# controller_pcb.net
KiCad netlist of a schematic drawn in EAGLE
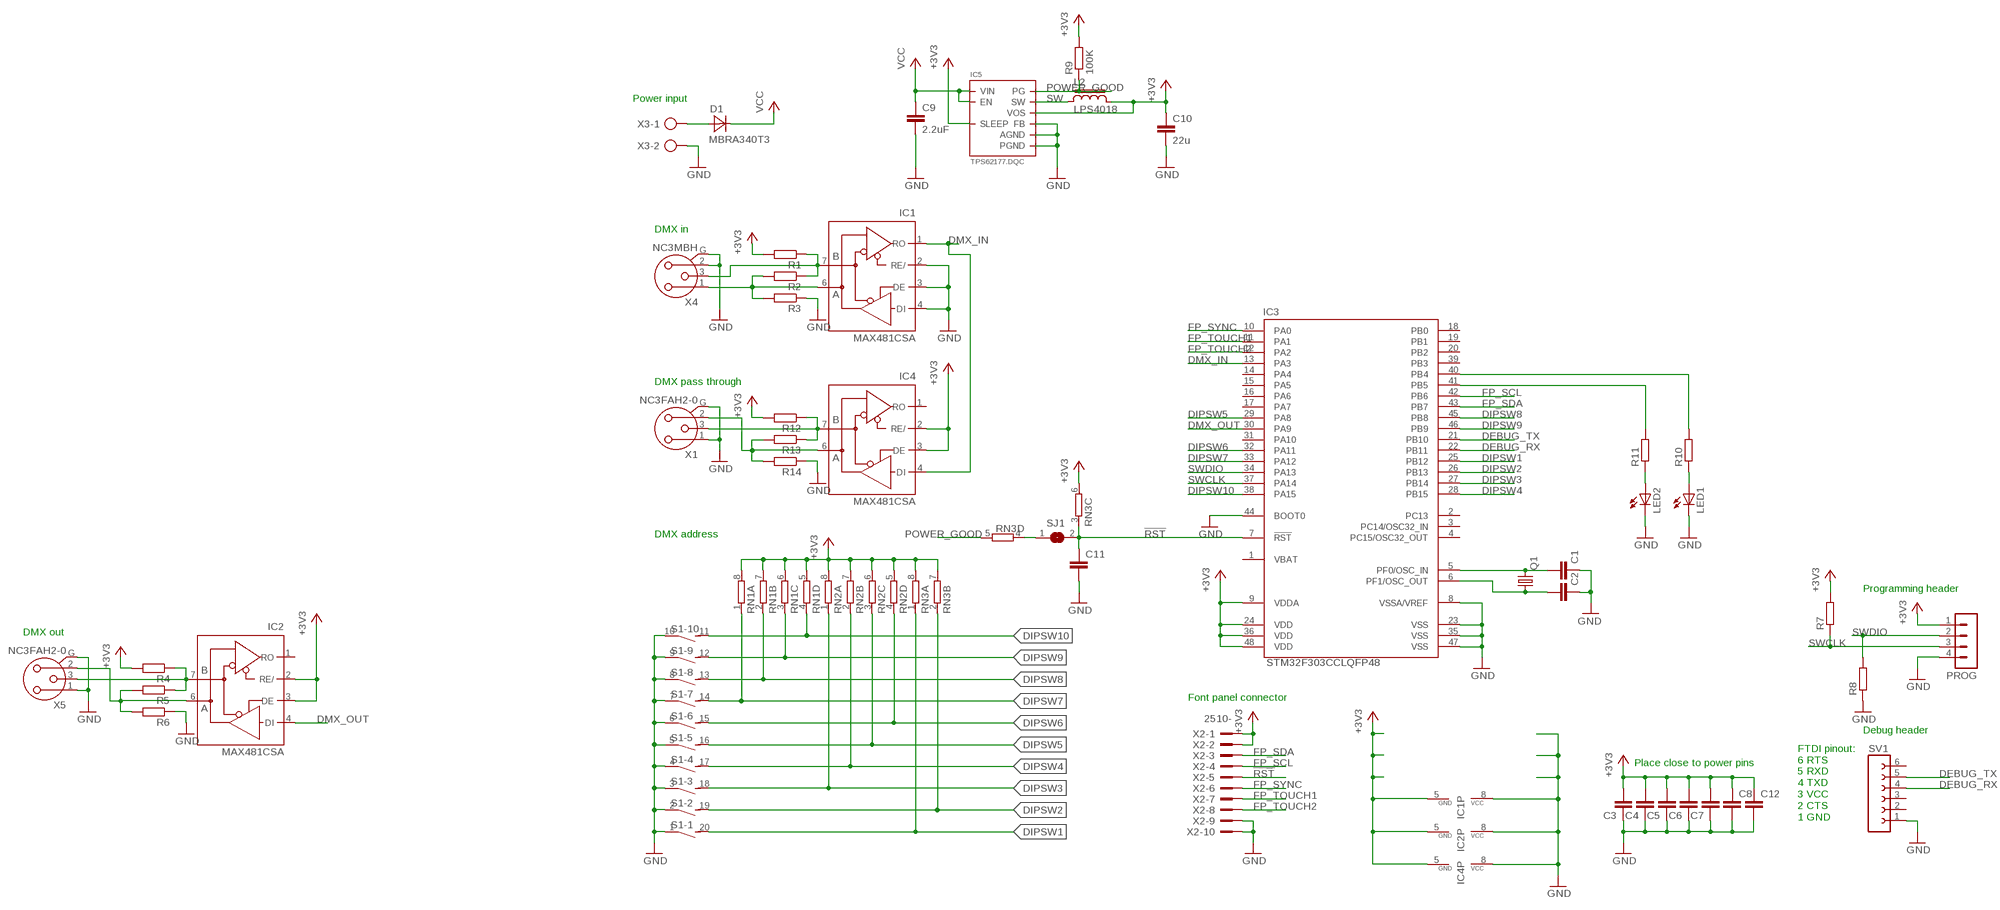
[diagram p0: schematic, sheet 1]

(export (version "E")
  (design (tool "Eeschema 10.0.6"))
  (components
    (comp (ref "C1")
      (value "C-EUC0603K")
      (footprint "eagle-import:C0603K")
      (libsource (lib "eagle-import") (part "C-EUC0603K"))
    )
    (comp (ref "C2")
      (value "C-EUC0603K")
      (footprint "eagle-import:C0603K")
      (libsource (lib "eagle-import") (part "C-EUC0603K"))
    )
    (comp (ref "C3")
      (value "C-EUC0603K")
      (footprint "eagle-import:C0603K")
      (libsource (lib "eagle-import") (part "C-EUC0603K"))
    )
    (comp (ref "C4")
      (value "C-EUC0603K")
      (footprint "eagle-import:C0603K")
      (libsource (lib "eagle-import") (part "C-EUC0603K"))
    )
    (comp (ref "C5")
      (value "C-EUC0603K")
      (footprint "eagle-import:C0603K")
      (libsource (lib "eagle-import") (part "C-EUC0603K"))
    )
    (comp (ref "C6")
      (value "C-EUC0603K")
      (footprint "eagle-import:C0603K")
      (libsource (lib "eagle-import") (part "C-EUC0603K"))
    )
    (comp (ref "C7")
      (value "C-EUC0603K")
      (footprint "eagle-import:C0603K")
      (libsource (lib "eagle-import") (part "C-EUC0603K"))
    )
    (comp (ref "C8")
      (value "C-EUC0603K")
      (footprint "eagle-import:C0603K")
      (libsource (lib "eagle-import") (part "C-EUC0603K"))
    )
    (comp (ref "C9")
      (value "2.2uF")
      (footprint "eagle-import:C1206")
      (libsource (lib "eagle-import") (part "C-EUC1206"))
    )
    (comp (ref "C10")
      (value "22u")
      (footprint "eagle-import:C1206")
      (libsource (lib "eagle-import") (part "C-EUC1206"))
    )
    (comp (ref "C11")
      (value "C-EUC0603K")
      (footprint "eagle-import:C0603K")
      (libsource (lib "eagle-import") (part "C-EUC0603K"))
    )
    (comp (ref "C12")
      (value "C-EUC0603K")
      (footprint "eagle-import:C0603K")
      (libsource (lib "eagle-import") (part "C-EUC0603K"))
    )
    (comp (ref "D1")
      (value "MBRA340T3")
      (footprint "eagle-import:SMA")
      (libsource (lib "eagle-import") (part "MBRA340T3"))
    )
    (comp (ref "IC1")
      (value "MAX481CSA")
      (footprint "eagle-import:SO08")
      (fields (field (name "MF") "MAXIM"))
      (libsource (lib "eagle-import") (part "MAX481CSA"))
    )
    (comp (ref "IC2")
      (value "MAX481CSA")
      (footprint "eagle-import:SO08")
      (fields (field (name "MF") "MAXIM"))
      (libsource (lib "eagle-import") (part "MAX481CSA"))
    )
    (comp (ref "IC3")
      (value "STM32F303CCLQFP48")
      (footprint "eagle-import:LQFP48")
      (libsource (lib "eagle-import") (part "STM32F303CCLQFP48"))
    )
    (comp (ref "IC4")
      (value "MAX481CSA")
      (footprint "eagle-import:SO08")
      (fields (field (name "MF") "MAXIM"))
      (libsource (lib "eagle-import") (part "MAX481CSA"))
    )
    (comp (ref "IC5")
      (value "TPS62177.DQC")
      (footprint "eagle-import:DQC")
      (libsource (lib "eagle-import") (part "TPS62177.DQC"))
    )
    (comp (ref "L2")
      (value "LPS4018")
      (footprint "eagle-import:LPS4018")
      (libsource (lib "eagle-import") (part "LPS4018"))
    )
    (comp (ref "LED1")
      (value "LEDCHIPLED_1206")
      (footprint "eagle-import:CHIPLED_1206")
      (libsource (lib "eagle-import") (part "LEDCHIPLED_1206"))
    )
    (comp (ref "LED2")
      (value "LEDCHIPLED_1206")
      (footprint "eagle-import:CHIPLED_1206")
      (libsource (lib "eagle-import") (part "LEDCHIPLED_1206"))
    )
    (comp (ref "PROG")
      (value "MA04-1")
      (footprint "eagle-import:MA04-1")
      (libsource (lib "eagle-import") (part "MA04-1"))
    )
    (comp (ref "Q1")
      (value "CRYSTALCTS406")
      (footprint "eagle-import:CTS406")
      (libsource (lib "eagle-import") (part "CRYSTALCTS406"))
    )
    (comp (ref "R1")
      (value "R-EU_R0603")
      (footprint "eagle-import:R0603")
      (libsource (lib "eagle-import") (part "R-EU_R0603"))
    )
    (comp (ref "R2")
      (value "R-EU_R0603")
      (footprint "eagle-import:R0603")
      (libsource (lib "eagle-import") (part "R-EU_R0603"))
    )
    (comp (ref "R3")
      (value "R-EU_R0603")
      (footprint "eagle-import:R0603")
      (libsource (lib "eagle-import") (part "R-EU_R0603"))
    )
    (comp (ref "R4")
      (value "R-EU_R0603")
      (footprint "eagle-import:R0603")
      (libsource (lib "eagle-import") (part "R-EU_R0603"))
    )
    (comp (ref "R5")
      (value "R-EU_R0603")
      (footprint "eagle-import:R0603")
      (libsource (lib "eagle-import") (part "R-EU_R0603"))
    )
    (comp (ref "R6")
      (value "R-EU_R0603")
      (footprint "eagle-import:R0603")
      (libsource (lib "eagle-import") (part "R-EU_R0603"))
    )
    (comp (ref "R7")
      (value "R-EU_R0603")
      (footprint "eagle-import:R0603")
      (libsource (lib "eagle-import") (part "R-EU_R0603"))
    )
    (comp (ref "R8")
      (value "R-EU_R0603")
      (footprint "eagle-import:R0603")
      (libsource (lib "eagle-import") (part "R-EU_R0603"))
    )
    (comp (ref "R9")
      (value "100K")
      (footprint "eagle-import:R0603")
      (libsource (lib "eagle-import") (part "R-EU_R0603"))
    )
    (comp (ref "R10")
      (value "R-EU_R0603")
      (footprint "eagle-import:R0603")
      (libsource (lib "eagle-import") (part "R-EU_R0603"))
    )
    (comp (ref "R11")
      (value "R-EU_R0603")
      (footprint "eagle-import:R0603")
      (libsource (lib "eagle-import") (part "R-EU_R0603"))
    )
    (comp (ref "R12")
      (value "R-EU_R0603")
      (footprint "eagle-import:R0603")
      (libsource (lib "eagle-import") (part "R-EU_R0603"))
    )
    (comp (ref "R13")
      (value "R-EU_R0603")
      (footprint "eagle-import:R0603")
      (libsource (lib "eagle-import") (part "R-EU_R0603"))
    )
    (comp (ref "R14")
      (value "R-EU_R0603")
      (footprint "eagle-import:R0603")
      (libsource (lib "eagle-import") (part "R-EU_R0603"))
    )
    (comp (ref "RN1")
      (value "4R-NCAY16")
      (footprint "eagle-import:CAY16")
      (libsource (lib "eagle-import") (part "4R-NCAY16"))
    )
    (comp (ref "RN2")
      (value "4R-NCAY16")
      (footprint "eagle-import:CAY16")
      (libsource (lib "eagle-import") (part "4R-NCAY16"))
    )
    (comp (ref "RN3")
      (value "4R-NCAY16")
      (footprint "eagle-import:CAY16")
      (libsource (lib "eagle-import") (part "4R-NCAY16"))
    )
    (comp (ref "S1")
      (value "DIP10SB")
      (footprint "eagle-import:DIP10SB")
      (libsource (lib "eagle-import") (part "DIP10SB"))
    )
    (comp (ref "SJ1") (value "SJ") (footprint "eagle-import:SJ") (libsource (lib "eagle-import") (part "SJ")))
    (comp (ref "SV1")
      (value "FE06-1")
      (footprint "eagle-import:FE06")
      (libsource (lib "eagle-import") (part "FE06-1"))
    )
    (comp (ref "X1")
      (value "NC3FAH2-0")
      (footprint "eagle-import:NC3FAH2-0")
      (fields (field (name "MPN") "NC3FAH-2-0"))
      (libsource (lib "eagle-import") (part "NC3FAH2-0"))
    )
    (comp (ref "X2")
      (value "2510-")
      (footprint "eagle-import:PAK100_2500-10")
      (fields (field (name "MF") "3M") (field (name "MPN") "2510-6002UB"))
      (libsource (lib "eagle-import") (part "2510-"))
    )
    (comp (ref "X3")
      (value "AK500/2")
      (footprint "eagle-import:AK500_2")
      (libsource (lib "eagle-import") (part "AK500/2"))
    )
    (comp (ref "X4")
      (value "NC3MBH")
      (footprint "eagle-import:NC3MBH")
      (fields (field (name "MF") "NEUTRIK"))
      (libsource (lib "eagle-import") (part "NC3MBH"))
    )
    (comp (ref "X5")
      (value "NC3FAH2-0")
      (footprint "eagle-import:NC3FAH2-0")
      (fields (field (name "MPN") "NC3FAH-2-0"))
      (libsource (lib "eagle-import") (part "NC3FAH2-0"))
    )
  )
  (nets
    (net (code "1") (name "+3V3") (class "Default")
      (node (ref "C10") (pin "1") (pinfunction "1_1") (pintype "passive"))
      (node (ref "C12") (pin "1") (pinfunction "1_1") (pintype "passive"))
      (node (ref "C3") (pin "2") (pinfunction "2_2") (pintype "passive"))
      (node (ref "C4") (pin "2") (pinfunction "2_2") (pintype "passive"))
      (node (ref "C5") (pin "2") (pinfunction "2_2") (pintype "passive"))
      (node (ref "C6") (pin "2") (pinfunction "2_2") (pintype "passive"))
      (node (ref "C7") (pin "2") (pinfunction "2_2") (pintype "passive"))
      (node (ref "C8") (pin "1") (pinfunction "1_1") (pintype "passive"))
      (node (ref "IC1") (pin "5") (pinfunction "GND_5") (pintype "power_in"))
      (node (ref "IC2") (pin "2") (pinfunction "RE/_2") (pintype "input"))
      (node (ref "IC2") (pin "3") (pinfunction "DE_3") (pintype "input"))
      (node (ref "IC2") (pin "5") (pinfunction "GND_5") (pintype "power_in"))
      (node (ref "IC3") (pin "24") (pinfunction "VDD_24") (pintype "power_in"))
      (node (ref "IC3") (pin "36") (pinfunction "VDD_36") (pintype "power_in"))
      (node (ref "IC3") (pin "48") (pinfunction "VDD_48") (pintype "power_in"))
      (node (ref "IC3") (pin "9") (pinfunction "VDDA_9") (pintype "power_in"))
      (node (ref "IC4") (pin "2") (pinfunction "RE/_2") (pintype "input"))
      (node (ref "IC4") (pin "3") (pinfunction "DE_3") (pintype "input"))
      (node (ref "IC4") (pin "5") (pinfunction "GND_5") (pintype "power_in"))
      (node (ref "IC5") (pin "10") (pinfunction "VOS_10") (pintype "bidirectional"))
      (node (ref "IC5") (pin "8") (pinfunction "SLEEP_8") (pintype "bidirectional"))
      (node (ref "L2") (pin "2") (pinfunction "2_2") (pintype "passive"))
      (node (ref "PROG") (pin "1") (pinfunction "1_1") (pintype "passive"))
      (node (ref "R1") (pin "2") (pinfunction "2_2") (pintype "passive"))
      (node (ref "R12") (pin "2") (pinfunction "2_2") (pintype "passive"))
      (node (ref "R4") (pin "2") (pinfunction "2_2") (pintype "passive"))
      (node (ref "R7") (pin "2") (pinfunction "2_2") (pintype "passive"))
      (node (ref "R9") (pin "2") (pinfunction "2_2") (pintype "passive"))
      (node (ref "RN1") (pin "5") (pinfunction "2_5") (pintype "passive"))
      (node (ref "RN1") (pin "6") (pinfunction "2_6") (pintype "passive"))
      (node (ref "RN1") (pin "7") (pinfunction "2_7") (pintype "passive"))
      (node (ref "RN1") (pin "8") (pinfunction "2_8") (pintype "passive"))
      (node (ref "RN2") (pin "5") (pinfunction "2_5") (pintype "passive"))
      (node (ref "RN2") (pin "6") (pinfunction "2_6") (pintype "passive"))
      (node (ref "RN2") (pin "7") (pinfunction "2_7") (pintype "passive"))
      (node (ref "RN2") (pin "8") (pinfunction "2_8") (pintype "passive"))
      (node (ref "RN3") (pin "6") (pinfunction "2_6") (pintype "passive"))
      (node (ref "RN3") (pin "7") (pinfunction "2_7") (pintype "passive"))
      (node (ref "RN3") (pin "8") (pinfunction "2_8") (pintype "passive"))
      (node (ref "X2") (pin "1") (pinfunction "KL_1") (pintype "passive"))
      (node (ref "X2") (pin "2") (pinfunction "KL_2") (pintype "passive"))
    )
    (net (code "2") (name "/DEBUG_RX") (class "Default")
      (node (ref "IC3") (pin "22") (pinfunction "PB11_22") (pintype "bidirectional"))
      (node (ref "SV1") (pin "4") (pinfunction "4_4") (pintype "passive"))
    )
    (net (code "3") (name "/DEBUG_TX") (class "Default")
      (node (ref "IC3") (pin "21") (pinfunction "PB10_21") (pintype "bidirectional"))
      (node (ref "SV1") (pin "5") (pinfunction "5_5") (pintype "passive"))
    )
    (net (code "4") (name "/DMX_IN") (class "Default")
      (node (ref "IC1") (pin "1") (pinfunction "RO_1") (pintype "output"))
      (node (ref "IC3") (pin "13") (pinfunction "PA3_13") (pintype "bidirectional"))
      (node (ref "IC4") (pin "4") (pinfunction "DI_4") (pintype "input"))
    )
    (net (code "5") (name "/DMX_OUT") (class "Default")
      (node (ref "IC2") (pin "4") (pinfunction "DI_4") (pintype "input"))
      (node (ref "IC3") (pin "30") (pinfunction "PA9_30") (pintype "bidirectional"))
    )
    (net (code "6") (name "/FP_SCL") (class "Default")
      (node (ref "IC3") (pin "42") (pinfunction "PB6_42") (pintype "bidirectional"))
      (node (ref "X2") (pin "4") (pinfunction "KL_4") (pintype "passive"))
    )
    (net (code "7") (name "/FP_SDA") (class "Default")
      (node (ref "IC3") (pin "43") (pinfunction "PB7_43") (pintype "bidirectional"))
      (node (ref "X2") (pin "3") (pinfunction "KL_3") (pintype "passive"))
    )
    (net (code "8") (name "/FP_SYNC") (class "Default")
      (node (ref "IC3") (pin "10") (pinfunction "PA0_10") (pintype "bidirectional"))
      (node (ref "X2") (pin "6") (pinfunction "KL_6") (pintype "passive"))
    )
    (net (code "9") (name "/FP_TOUCH1") (class "Default")
      (node (ref "IC3") (pin "11") (pinfunction "PA1_11") (pintype "bidirectional"))
      (node (ref "X2") (pin "7") (pinfunction "KL_7") (pintype "passive"))
    )
    (net (code "10") (name "/FP_TOUCH2") (class "Default")
      (node (ref "IC3") (pin "12") (pinfunction "PA2_12") (pintype "bidirectional"))
      (node (ref "X2") (pin "8") (pinfunction "KL_8") (pintype "passive"))
    )
    (net (code "11") (name "/POWER_GOOD") (class "Default")
      (node (ref "IC5") (pin "7") (pinfunction "PG_7") (pintype "bidirectional"))
      (node (ref "R9") (pin "1") (pinfunction "1_1") (pintype "passive"))
      (node (ref "RN3") (pin "5") (pinfunction "2_5") (pintype "passive"))
    )
    (net (code "12") (name "/SW") (class "Default")
      (node (ref "IC5") (pin "9") (pinfunction "SW_9") (pintype "bidirectional"))
      (node (ref "L2") (pin "1") (pinfunction "1_1") (pintype "passive"))
    )
    (net (code "13") (name "/SWCLK") (class "Default")
      (node (ref "IC3") (pin "37") (pinfunction "PA14_37") (pintype "bidirectional"))
      (node (ref "PROG") (pin "3") (pinfunction "3_3") (pintype "passive"))
      (node (ref "R7") (pin "1") (pinfunction "1_1") (pintype "passive"))
    )
    (net (code "14") (name "/SWDIO") (class "Default")
      (node (ref "IC3") (pin "34") (pinfunction "PA13_34") (pintype "bidirectional"))
      (node (ref "PROG") (pin "2") (pinfunction "2_2") (pintype "passive"))
      (node (ref "R8") (pin "2") (pinfunction "2_2") (pintype "passive"))
    )
    (net (code "15") (name "/~{RST}") (class "Default")
      (node (ref "C11") (pin "1") (pinfunction "1_1") (pintype "passive"))
      (node (ref "IC3") (pin "7") (pinfunction "~{RST}_7") (pintype "bidirectional"))
      (node (ref "RN3") (pin "3") (pinfunction "1_3") (pintype "passive"))
      (node (ref "SJ1") (pin "2") (pinfunction "2_2") (pintype "passive"))
      (node (ref "X2") (pin "5") (pinfunction "KL_5") (pintype "passive"))
    )
    (net (code "16") (name "DIPSW1") (class "Default")
      (node (ref "IC3") (pin "25") (pinfunction "PB12_25") (pintype "bidirectional"))
      (node (ref "RN3") (pin "1") (pinfunction "1_1") (pintype "passive"))
      (node (ref "S1") (pin "20") (pinfunction "2_20") (pintype "passive"))
    )
    (net (code "17") (name "DIPSW2") (class "Default")
      (node (ref "IC3") (pin "26") (pinfunction "PB13_26") (pintype "bidirectional"))
      (node (ref "RN3") (pin "2") (pinfunction "1_2") (pintype "passive"))
      (node (ref "S1") (pin "19") (pinfunction "2_19") (pintype "passive"))
    )
    (net (code "18") (name "DIPSW3") (class "Default")
      (node (ref "IC3") (pin "27") (pinfunction "PB14_27") (pintype "bidirectional"))
      (node (ref "RN2") (pin "1") (pinfunction "1_1") (pintype "passive"))
      (node (ref "S1") (pin "18") (pinfunction "2_18") (pintype "passive"))
    )
    (net (code "19") (name "DIPSW4") (class "Default")
      (node (ref "IC3") (pin "28") (pinfunction "PB15_28") (pintype "bidirectional"))
      (node (ref "RN2") (pin "2") (pinfunction "1_2") (pintype "passive"))
      (node (ref "S1") (pin "17") (pinfunction "2_17") (pintype "passive"))
    )
    (net (code "20") (name "DIPSW5") (class "Default")
      (node (ref "IC3") (pin "29") (pinfunction "PA8_29") (pintype "bidirectional"))
      (node (ref "RN2") (pin "3") (pinfunction "1_3") (pintype "passive"))
      (node (ref "S1") (pin "16") (pinfunction "2_16") (pintype "passive"))
    )
    (net (code "21") (name "DIPSW6") (class "Default")
      (node (ref "IC3") (pin "32") (pinfunction "PA11_32") (pintype "bidirectional"))
      (node (ref "RN2") (pin "4") (pinfunction "1_4") (pintype "passive"))
      (node (ref "S1") (pin "15") (pinfunction "2_15") (pintype "passive"))
    )
    (net (code "22") (name "DIPSW7") (class "Default")
      (node (ref "IC3") (pin "33") (pinfunction "PA12_33") (pintype "bidirectional"))
      (node (ref "RN1") (pin "1") (pinfunction "1_1") (pintype "passive"))
      (node (ref "S1") (pin "14") (pinfunction "2_14") (pintype "passive"))
    )
    (net (code "23") (name "DIPSW8") (class "Default")
      (node (ref "IC3") (pin "45") (pinfunction "PB8_45") (pintype "bidirectional"))
      (node (ref "RN1") (pin "2") (pinfunction "1_2") (pintype "passive"))
      (node (ref "S1") (pin "13") (pinfunction "2_13") (pintype "passive"))
    )
    (net (code "24") (name "DIPSW9") (class "Default")
      (node (ref "IC3") (pin "46") (pinfunction "PB9_46") (pintype "bidirectional"))
      (node (ref "RN1") (pin "3") (pinfunction "1_3") (pintype "passive"))
      (node (ref "S1") (pin "12") (pinfunction "2_12") (pintype "passive"))
    )
    (net (code "25") (name "DIPSW10") (class "Default")
      (node (ref "IC3") (pin "38") (pinfunction "PA15_38") (pintype "bidirectional"))
      (node (ref "RN1") (pin "4") (pinfunction "1_4") (pintype "passive"))
      (node (ref "S1") (pin "11") (pinfunction "2_11") (pintype "passive"))
    )
    (net (code "26") (name "GND") (class "Default")
      (node (ref "C1") (pin "1") (pinfunction "1_1") (pintype "passive"))
      (node (ref "C10") (pin "2") (pinfunction "2_2") (pintype "passive"))
      (node (ref "C11") (pin "2") (pinfunction "2_2") (pintype "passive"))
      (node (ref "C12") (pin "2") (pinfunction "2_2") (pintype "passive"))
      (node (ref "C2") (pin "1") (pinfunction "1_1") (pintype "passive"))
      (node (ref "C3") (pin "1") (pinfunction "1_1") (pintype "passive"))
      (node (ref "C4") (pin "1") (pinfunction "1_1") (pintype "passive"))
      (node (ref "C5") (pin "1") (pinfunction "1_1") (pintype "passive"))
      (node (ref "C6") (pin "1") (pinfunction "1_1") (pintype "passive"))
      (node (ref "C7") (pin "1") (pinfunction "1_1") (pintype "passive"))
      (node (ref "C8") (pin "2") (pinfunction "2_2") (pintype "passive"))
      (node (ref "C9") (pin "2") (pinfunction "2_2") (pintype "passive"))
      (node (ref "IC1") (pin "2") (pinfunction "RE/_2") (pintype "input"))
      (node (ref "IC1") (pin "3") (pinfunction "DE_3") (pintype "input"))
      (node (ref "IC1") (pin "4") (pinfunction "DI_4") (pintype "input"))
      (node (ref "IC1") (pin "8") (pinfunction "VCC_8") (pintype "power_in"))
      (node (ref "IC2") (pin "8") (pinfunction "VCC_8") (pintype "power_in"))
      (node (ref "IC3") (pin "23") (pinfunction "VSS_23") (pintype "power_in"))
      (node (ref "IC3") (pin "35") (pinfunction "VSS_35") (pintype "power_in"))
      (node (ref "IC3") (pin "44") (pinfunction "BOOT0_44") (pintype "bidirectional"))
      (node (ref "IC3") (pin "47") (pinfunction "VSS_47") (pintype "power_in"))
      (node (ref "IC3") (pin "8") (pinfunction "VSSA/VREF_8") (pintype "power_in"))
      (node (ref "IC4") (pin "8") (pinfunction "VCC_8") (pintype "power_in"))
      (node (ref "IC5") (pin "1") (pinfunction "PGND_1") (pintype "bidirectional"))
      (node (ref "IC5") (pin "5") (pinfunction "FB_5") (pintype "bidirectional"))
      (node (ref "IC5") (pin "6") (pinfunction "AGND_6") (pintype "bidirectional"))
      (node (ref "IC5") (pin "PAD") (pinfunction "PGND_PAD") (pintype "bidirectional"))
      (node (ref "LED1") (pin "C") (pinfunction "C_C") (pintype "passive"))
      (node (ref "LED2") (pin "C") (pinfunction "C_C") (pintype "passive"))
      (node (ref "PROG") (pin "4") (pinfunction "4_4") (pintype "passive"))
      (node (ref "R14") (pin "1") (pinfunction "1_1") (pintype "passive"))
      (node (ref "R3") (pin "1") (pinfunction "1_1") (pintype "passive"))
      (node (ref "R6") (pin "1") (pinfunction "1_1") (pintype "passive"))
      (node (ref "R8") (pin "1") (pinfunction "1_1") (pintype "passive"))
      (node (ref "S1") (pin "1") (pinfunction "1_1") (pintype "passive"))
      (node (ref "S1") (pin "10") (pinfunction "1_10") (pintype "passive"))
      (node (ref "S1") (pin "2") (pinfunction "1_2") (pintype "passive"))
      (node (ref "S1") (pin "3") (pinfunction "1_3") (pintype "passive"))
      (node (ref "S1") (pin "4") (pinfunction "1_4") (pintype "passive"))
      (node (ref "S1") (pin "5") (pinfunction "1_5") (pintype "passive"))
      (node (ref "S1") (pin "6") (pinfunction "1_6") (pintype "passive"))
      (node (ref "S1") (pin "7") (pinfunction "1_7") (pintype "passive"))
      (node (ref "S1") (pin "8") (pinfunction "1_8") (pintype "passive"))
      (node (ref "S1") (pin "9") (pinfunction "1_9") (pintype "passive"))
      (node (ref "SV1") (pin "1") (pinfunction "1_1") (pintype "passive"))
      (node (ref "X1") (pin "1") (pinfunction "1_1") (pintype "passive"))
      (node (ref "X1") (pin "G") (pinfunction "G_G") (pintype "passive"))
      (node (ref "X2") (pin "10") (pinfunction "KL_10") (pintype "passive"))
      (node (ref "X2") (pin "9") (pinfunction "KL_9") (pintype "passive"))
      (node (ref "X3") (pin "2") (pinfunction "KL_2") (pintype "passive"))
      (node (ref "X4") (pin "2") (pinfunction "2_2") (pintype "passive"))
      (node (ref "X4") (pin "G") (pinfunction "G_G") (pintype "passive"))
      (node (ref "X5") (pin "1") (pinfunction "1_1") (pintype "passive"))
      (node (ref "X5") (pin "G") (pinfunction "G_G") (pintype "passive"))
    )
    (net (code "27") (name "Net-(IC1A-A)") (class "Default")
      (node (ref "IC1") (pin "6") (pinfunction "A_6") (pintype "passive"))
      (node (ref "R2") (pin "2") (pinfunction "2_2") (pintype "passive"))
      (node (ref "R3") (pin "2") (pinfunction "2_2") (pintype "passive"))
      (node (ref "X4") (pin "1") (pinfunction "1_1") (pintype "passive"))
    )
    (net (code "28") (name "Net-(IC1A-B)") (class "Default")
      (node (ref "IC1") (pin "7") (pinfunction "B_7") (pintype "passive"))
      (node (ref "R1") (pin "1") (pinfunction "1_1") (pintype "passive"))
      (node (ref "R2") (pin "1") (pinfunction "1_1") (pintype "passive"))
      (node (ref "X4") (pin "3") (pinfunction "3_3") (pintype "passive"))
    )
    (net (code "29") (name "Net-(IC2A-A)") (class "Default")
      (node (ref "IC2") (pin "6") (pinfunction "A_6") (pintype "passive"))
      (node (ref "R5") (pin "2") (pinfunction "2_2") (pintype "passive"))
      (node (ref "R6") (pin "2") (pinfunction "2_2") (pintype "passive"))
      (node (ref "X5") (pin "2") (pinfunction "2_2") (pintype "passive"))
    )
    (net (code "30") (name "Net-(IC2A-B)") (class "Default")
      (node (ref "IC2") (pin "7") (pinfunction "B_7") (pintype "passive"))
      (node (ref "R4") (pin "1") (pinfunction "1_1") (pintype "passive"))
      (node (ref "R5") (pin "1") (pinfunction "1_1") (pintype "passive"))
      (node (ref "X5") (pin "3") (pinfunction "3_3") (pintype "passive"))
    )
    (net (code "31") (name "Net-(IC3-PB4)") (class "Default")
      (node (ref "IC3") (pin "40") (pinfunction "PB4_40") (pintype "bidirectional"))
      (node (ref "R10") (pin "2") (pinfunction "2_2") (pintype "passive"))
    )
    (net (code "32") (name "Net-(IC3-PB5)") (class "Default")
      (node (ref "IC3") (pin "41") (pinfunction "PB5_41") (pintype "bidirectional"))
      (node (ref "R11") (pin "2") (pinfunction "2_2") (pintype "passive"))
    )
    (net (code "33") (name "Net-(IC3-PF0{slash}OSC_IN)") (class "Default")
      (node (ref "C1") (pin "2") (pinfunction "2_2") (pintype "passive"))
      (node (ref "IC3") (pin "5") (pinfunction "PF0/OSC_IN_5") (pintype "bidirectional"))
      (node (ref "Q1") (pin "3") (pinfunction "2_3") (pintype "passive"))
    )
    (net (code "34") (name "Net-(IC3-PF1{slash}OSC_OUT)") (class "Default")
      (node (ref "C2") (pin "2") (pinfunction "2_2") (pintype "passive"))
      (node (ref "IC3") (pin "6") (pinfunction "PF1/OSC_OUT_6") (pintype "bidirectional"))
      (node (ref "Q1") (pin "1") (pinfunction "1_1") (pintype "passive"))
    )
    (net (code "35") (name "Net-(IC4A-A)") (class "Default")
      (node (ref "IC4") (pin "6") (pinfunction "A_6") (pintype "passive"))
      (node (ref "R13") (pin "2") (pinfunction "2_2") (pintype "passive"))
      (node (ref "R14") (pin "2") (pinfunction "2_2") (pintype "passive"))
      (node (ref "X1") (pin "2") (pinfunction "2_2") (pintype "passive"))
    )
    (net (code "36") (name "Net-(IC4A-B)") (class "Default")
      (node (ref "IC4") (pin "7") (pinfunction "B_7") (pintype "passive"))
      (node (ref "R12") (pin "1") (pinfunction "1_1") (pintype "passive"))
      (node (ref "R13") (pin "1") (pinfunction "1_1") (pintype "passive"))
      (node (ref "X1") (pin "3") (pinfunction "3_3") (pintype "passive"))
    )
    (net (code "37") (name "Net-(LED1-PadA)") (class "Default")
      (node (ref "LED1") (pin "A") (pinfunction "A_A") (pintype "passive"))
      (node (ref "R10") (pin "1") (pinfunction "1_1") (pintype "passive"))
    )
    (net (code "38") (name "Net-(LED2-PadA)") (class "Default")
      (node (ref "LED2") (pin "A") (pinfunction "A_A") (pintype "passive"))
      (node (ref "R11") (pin "1") (pinfunction "1_1") (pintype "passive"))
    )
    (net (code "39") (name "Net-(RN3D-1)") (class "Default")
      (node (ref "RN3") (pin "4") (pinfunction "1_4") (pintype "passive"))
      (node (ref "SJ1") (pin "1") (pinfunction "1_1") (pintype "passive"))
    )
    (net (code "40") (name "Net-(X3A-KL)") (class "Default")
      (node (ref "D1") (pin "A") (pinfunction "A_A") (pintype "passive"))
      (node (ref "X3") (pin "1") (pinfunction "KL_1") (pintype "passive"))
    )
    (net (code "41") (name "VCC") (class "Default")
      (node (ref "C9") (pin "1") (pinfunction "1_1") (pintype "passive"))
      (node (ref "D1") (pin "C") (pinfunction "C_C") (pintype "passive"))
      (node (ref "IC5") (pin "2") (pinfunction "VIN_2") (pintype "bidirectional"))
      (node (ref "IC5") (pin "3") (pinfunction "EN_3") (pintype "bidirectional"))
    )
    (net (code "42") (name "unconnected-(IC2A-RO-Pad1)") (class "Default")
      (node (ref "IC2") (pin "1") (pinfunction "RO_1") (pintype "output"))
    )
    (net (code "43") (name "unconnected-(IC3-PA4-Pad14)") (class "Default")
      (node (ref "IC3") (pin "14") (pinfunction "PA4_14") (pintype "bidirectional"))
    )
    (net (code "44") (name "unconnected-(IC3-PA5-Pad15)") (class "Default")
      (node (ref "IC3") (pin "15") (pinfunction "PA5_15") (pintype "bidirectional"))
    )
    (net (code "45") (name "unconnected-(IC3-PA6-Pad16)") (class "Default")
      (node (ref "IC3") (pin "16") (pinfunction "PA6_16") (pintype "bidirectional"))
    )
    (net (code "46") (name "unconnected-(IC3-PA7-Pad17)") (class "Default")
      (node (ref "IC3") (pin "17") (pinfunction "PA7_17") (pintype "bidirectional"))
    )
    (net (code "47") (name "unconnected-(IC3-PA10-Pad31)") (class "Default")
      (node (ref "IC3") (pin "31") (pinfunction "PA10_31") (pintype "bidirectional"))
    )
    (net (code "48") (name "unconnected-(IC3-PB0-Pad18)") (class "Default")
      (node (ref "IC3") (pin "18") (pinfunction "PB0_18") (pintype "bidirectional"))
    )
    (net (code "49") (name "unconnected-(IC3-PB1-Pad19)") (class "Default")
      (node (ref "IC3") (pin "19") (pinfunction "PB1_19") (pintype "bidirectional"))
    )
    (net (code "50") (name "unconnected-(IC3-PB2-Pad20)") (class "Default")
      (node (ref "IC3") (pin "20") (pinfunction "PB2_20") (pintype "bidirectional"))
    )
    (net (code "51") (name "unconnected-(IC3-PB3-Pad39)") (class "Default")
      (node (ref "IC3") (pin "39") (pinfunction "PB3_39") (pintype "bidirectional"))
    )
    (net (code "52") (name "unconnected-(IC3-PC13-Pad2)") (class "Default")
      (node (ref "IC3") (pin "2") (pinfunction "PC13_2") (pintype "bidirectional"))
    )
    (net (code "53") (name "unconnected-(IC3-PC14{slash}OSC32_IN-Pad3)") (class "Default")
      (node (ref "IC3") (pin "3") (pinfunction "PC14/OSC32_IN_3") (pintype "bidirectional"))
    )
    (net (code "54") (name "unconnected-(IC3-PC15{slash}OSC32_OUT-Pad4)") (class "Default")
      (node (ref "IC3") (pin "4") (pinfunction "PC15/OSC32_OUT_4") (pintype "bidirectional"))
    )
    (net (code "55") (name "unconnected-(IC3-VBAT-Pad1)") (class "Default")
      (node (ref "IC3") (pin "1") (pinfunction "VBAT_1") (pintype "bidirectional"))
    )
    (net (code "56") (name "unconnected-(IC4A-RO-Pad1)") (class "Default")
      (node (ref "IC4") (pin "1") (pinfunction "RO_1") (pintype "output"))
    )
    (net (code "57") (name "unconnected-(SV1-Pad2)") (class "Default")
      (node (ref "SV1") (pin "2") (pinfunction "2_2") (pintype "passive"))
    )
    (net (code "58") (name "unconnected-(SV1-Pad3)") (class "Default")
      (node (ref "SV1") (pin "3") (pinfunction "3_3") (pintype "passive"))
    )
    (net (code "59") (name "unconnected-(SV1-Pad6)") (class "Default")
      (node (ref "SV1") (pin "6") (pinfunction "6_6") (pintype "passive"))
    )
  )
)
